# MicroMultimeter_USB_Sch.net
KiCad netlist of a schematic drawn in Altium Designer
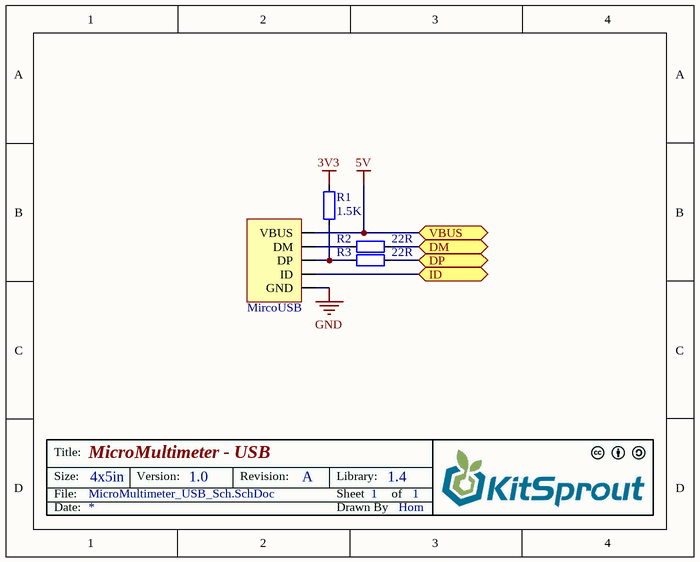
[diagram p0: MicroMultimeter_USB_Sch.SchDoc]

(export (version "E")
  (design (tool "Eeschema 10.0.6"))
  (components
    (comp (ref "MircoUSB")
      (value "USB_Micro")
      (footprint "Micro_USB")
      (description "USB")
      (libsource (lib "MicroMultimeter_SIGNAL_Sch_Lib") (part "USB_Micro"))
    )
    (comp (ref "R1")
      (value "1.5K")
      (footprint "RES_0603")
      (description "Resistor")
      (fields (field (name "Comment") "Res_0603"))
      (libsource (lib "") (part "Res_0603_1"))
    )
    (comp (ref "R2")
      (value "22R")
      (footprint "RES_0603")
      (description "Resistor")
      (fields (field (name "Comment") "Res_0603"))
      (libsource (lib "SCH_Passive") (part "Res_0603"))
    )
    (comp (ref "R3")
      (value "22R")
      (footprint "RES_0603")
      (description "Resistor")
      (fields (field (name "Comment") "Res_0603"))
      (libsource (lib "SCH_Passive") (part "Res_0603"))
    )
  )
  (nets
    (net (code "1") (name "/DM") (class "Default")
      (node (ref "R2") (pin "2") (pinfunction "2_2") (pintype "passive"))
    )
    (net (code "2") (name "/DP") (class "Default")
      (node (ref "R3") (pin "2") (pinfunction "2_2") (pintype "passive"))
    )
    (net (code "3") (name "/ID") (class "Default")
      (node (ref "MircoUSB") (pin "4") (pinfunction "ID_4") (pintype "passive"))
    )
    (net (code "4") (name "3V3") (class "Default")
      (node (ref "R1") (pin "1") (pinfunction "1_1") (pintype "passive"))
    )
    (net (code "5") (name "5V") (class "Default")
      (node (ref "MircoUSB") (pin "1") (pinfunction "VBUS_1") (pintype "passive"))
    )
    (net (code "6") (name "GND") (class "Default")
      (node (ref "MircoUSB") (pin "5") (pinfunction "GND_5") (pintype "passive"))
    )
    (net (code "7") (name "Net-(MircoUSB-DM)") (class "Default")
      (node (ref "MircoUSB") (pin "2") (pinfunction "DM_2") (pintype "passive"))
      (node (ref "R2") (pin "1") (pinfunction "1_1") (pintype "passive"))
    )
    (net (code "8") (name "Net-(MircoUSB-DP)") (class "Default")
      (node (ref "MircoUSB") (pin "3") (pinfunction "DP_3") (pintype "passive"))
      (node (ref "R1") (pin "2") (pinfunction "2_2") (pintype "passive"))
      (node (ref "R3") (pin "1") (pinfunction "1_1") (pintype "passive"))
    )
  )
)
